# display.net
KiCad netlist of a schematic drawn in EAGLE
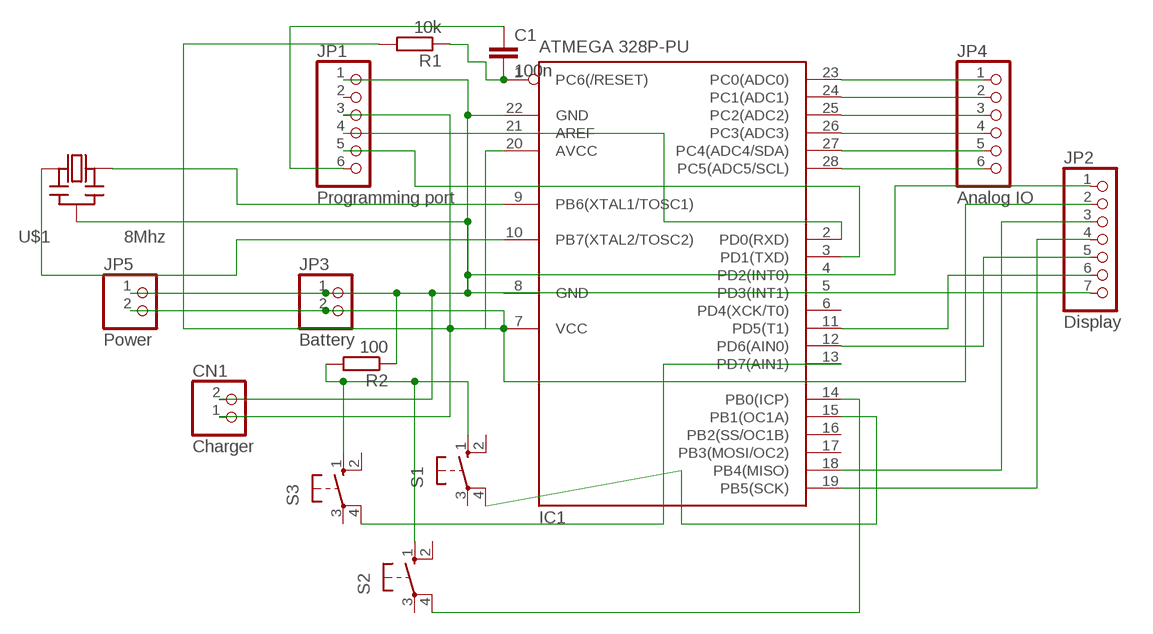
[diagram p0: schematic, sheet 1]

(export (version "E")
  (design (tool "Eeschema 10.0.6"))
  (components
    (comp (ref "C1")
      (value "100n")
      (footprint "eagle-import:C050-025X075")
      (libsource (lib "eagle-import") (part "C-EU050-025X075"))
    )
    (comp (ref "CN1")
      (value "Charger")
      (footprint "eagle-import:JST-PH-2-THM-RA")
      (libsource (lib "eagle-import") (part "JST_2PIN-THM-RA"))
    )
    (comp (ref "IC1")
      (value "ATMEGA 328P-PU")
      (footprint "eagle-import:DIL28-3")
      (libsource (lib "eagle-import") (part "MEGA8-P"))
    )
    (comp (ref "JP1")
      (value "Programming port")
      (footprint "eagle-import:1X06_90")
      (libsource (lib "eagle-import") (part "PINHD-1X6/90"))
    )
    (comp (ref "JP2")
      (value "Display")
      (footprint "eagle-import:1X07")
      (libsource (lib "eagle-import") (part "PINHD-1X7"))
    )
    (comp (ref "JP3")
      (value "Battery")
      (footprint "eagle-import:1X02")
      (libsource (lib "eagle-import") (part "PINHD-1X2"))
    )
    (comp (ref "JP4")
      (value "Analog IO")
      (footprint "eagle-import:1X06-CLEAN")
      (libsource (lib "eagle-import") (part "PINHD-1X6CLEAN"))
    )
    (comp (ref "JP5")
      (value "Power")
      (footprint "eagle-import:1X02")
      (libsource (lib "eagle-import") (part "PINHD-1X2"))
    )
    (comp (ref "R1")
      (value "10k")
      (footprint "eagle-import:0204_7")
      (libsource (lib "eagle-import") (part "R-EU_0204/7"))
    )
    (comp (ref "R2")
      (value "100")
      (footprint "eagle-import:0204_7")
      (libsource (lib "eagle-import") (part "R-EU_0204/7"))
    )
    (comp (ref "S1")
      (value "10-XX")
      (footprint "eagle-import:B3F-10XX")
      (fields (field (name "MPN") "B3F-1000"))
      (libsource (lib "eagle-import") (part "10-XX"))
    )
    (comp (ref "S2")
      (value "10-XX")
      (footprint "eagle-import:B3F-10XX")
      (fields
        (field (name "MPN") "B3F-1000")
        (field (name "MPN_1") "B3F-1000")
        (field (name "OC_FARNELL") "176432")
        (field (name "OC_NEWARK") "36M3542")
      )
      (libsource (lib "eagle-import") (part "10-XX"))
    )
    (comp (ref "S3")
      (value "10-XX")
      (footprint "eagle-import:B3F-10XX")
      (fields (field (name "MPN") "B3F-1000"))
      (libsource (lib "eagle-import") (part "10-XX"))
    )
    (comp (ref "U$1")
      (value "8Mhz")
      (footprint "eagle-import:CERM_OSC")
      (libsource (lib "eagle-import") (part "CERMOSCILL-THM"))
    )
  )
  (nets
    (net (code "1") (name "Net-(C1-Pad1)") (class "Default")
      (node (ref "C1") (pin "1") (pinfunction "1_1") (pintype "passive"))
      (node (ref "JP1") (pin "6") (pinfunction "6_6") (pintype "passive"))
    )
    (net (code "2") (name "Net-(CN1-1)") (class "Default")
      (node (ref "CN1") (pin "2") (pinfunction "1_2") (pintype "passive"))
      (node (ref "IC1") (pin "22") (pinfunction "GND_22") (pintype "power_in"))
      (node (ref "IC1") (pin "8") (pinfunction "GND_8") (pintype "power_in"))
      (node (ref "JP1") (pin "1") (pinfunction "1_1") (pintype "passive"))
      (node (ref "JP2") (pin "1") (pinfunction "1_1") (pintype "passive"))
      (node (ref "JP2") (pin "7") (pinfunction "7_7") (pintype "passive"))
      (node (ref "JP3") (pin "1") (pinfunction "1_1") (pintype "passive"))
      (node (ref "JP5") (pin "1") (pinfunction "1_1") (pintype "passive"))
      (node (ref "R2") (pin "1") (pinfunction "1_1") (pintype "passive"))
      (node (ref "U$1") (pin "P$2") (pinfunction "GND_P$2") (pintype "bidirectional"))
    )
    (net (code "3") (name "Net-(CN1-2)") (class "Default")
      (node (ref "CN1") (pin "1") (pinfunction "2_1") (pintype "passive"))
      (node (ref "IC1") (pin "20") (pinfunction "AVCC_20") (pintype "power_in"))
      (node (ref "IC1") (pin "7") (pinfunction "VCC_7") (pintype "power_in"))
      (node (ref "JP1") (pin "3") (pinfunction "3_3") (pintype "passive"))
      (node (ref "JP2") (pin "2") (pinfunction "2_2") (pintype "passive"))
      (node (ref "JP3") (pin "2") (pinfunction "2_2") (pintype "passive"))
      (node (ref "JP5") (pin "2") (pinfunction "2_2") (pintype "passive"))
      (node (ref "R1") (pin "2") (pinfunction "2_2") (pintype "passive"))
    )
    (net (code "4") (name "Net-(IC1-PB0(ICP))") (class "Default")
      (node (ref "IC1") (pin "14") (pinfunction "PB0(ICP)_14") (pintype "bidirectional"))
      (node (ref "S2") (pin "4") (pinfunction "P1_4") (pintype "passive"))
    )
    (net (code "5") (name "Net-(IC1-PB1(OC1A))") (class "Default")
      (node (ref "IC1") (pin "15") (pinfunction "PB1(OC1A)_15") (pintype "bidirectional"))
      (node (ref "S1") (pin "4") (pinfunction "P1_4") (pintype "passive"))
    )
    (net (code "6") (name "Net-(IC1-PB4(MISO))") (class "Default")
      (node (ref "IC1") (pin "18") (pinfunction "PB4(MISO)_18") (pintype "bidirectional"))
      (node (ref "JP2") (pin "3") (pinfunction "3_3") (pintype "passive"))
    )
    (net (code "7") (name "Net-(IC1-PB5(SCK))") (class "Default")
      (node (ref "IC1") (pin "19") (pinfunction "PB5(SCK)_19") (pintype "bidirectional"))
      (node (ref "JP2") (pin "4") (pinfunction "4_4") (pintype "passive"))
    )
    (net (code "8") (name "Net-(IC1-PB6(XTAL1{slash}TOSC1))") (class "Default")
      (node (ref "IC1") (pin "9") (pinfunction "PB6(XTAL1/TOSC1)_9") (pintype "bidirectional"))
      (node (ref "U$1") (pin "P$3") (pinfunction "OUT_P$3") (pintype "bidirectional"))
    )
    (net (code "9") (name "Net-(IC1-PB7(XTAL2{slash}TOSC2))") (class "Default")
      (node (ref "IC1") (pin "10") (pinfunction "PB7(XTAL2/TOSC2)_10") (pintype "bidirectional"))
      (node (ref "U$1") (pin "P$1") (pinfunction "IN_P$1") (pintype "bidirectional"))
    )
    (net (code "10") (name "Net-(IC1-PC0(ADC0))") (class "Default")
      (node (ref "IC1") (pin "23") (pinfunction "PC0(ADC0)_23") (pintype "bidirectional"))
      (node (ref "JP4") (pin "1") (pinfunction "1_1") (pintype "passive"))
    )
    (net (code "11") (name "Net-(IC1-PC1(ADC1))") (class "Default")
      (node (ref "IC1") (pin "24") (pinfunction "PC1(ADC1)_24") (pintype "bidirectional"))
      (node (ref "JP4") (pin "2") (pinfunction "2_2") (pintype "passive"))
    )
    (net (code "12") (name "Net-(IC1-PC2(ADC2))") (class "Default")
      (node (ref "IC1") (pin "25") (pinfunction "PC2(ADC2)_25") (pintype "bidirectional"))
      (node (ref "JP4") (pin "3") (pinfunction "3_3") (pintype "passive"))
    )
    (net (code "13") (name "Net-(IC1-PC3(ADC3))") (class "Default")
      (node (ref "IC1") (pin "26") (pinfunction "PC3(ADC3)_26") (pintype "bidirectional"))
      (node (ref "JP4") (pin "4") (pinfunction "4_4") (pintype "passive"))
    )
    (net (code "14") (name "Net-(IC1-PC4(ADC4{slash}SDA))") (class "Default")
      (node (ref "IC1") (pin "27") (pinfunction "PC4(ADC4/SDA)_27") (pintype "bidirectional"))
      (node (ref "JP4") (pin "5") (pinfunction "5_5") (pintype "passive"))
    )
    (net (code "15") (name "Net-(IC1-PC5(ADC5{slash}SCL))") (class "Default")
      (node (ref "IC1") (pin "28") (pinfunction "PC5(ADC5/SCL)_28") (pintype "bidirectional"))
      (node (ref "JP4") (pin "6") (pinfunction "6_6") (pintype "passive"))
    )
    (net (code "16") (name "Net-(IC1-PC6({slash}RESET))") (class "Default")
      (node (ref "C1") (pin "2") (pinfunction "2_2") (pintype "passive"))
      (node (ref "IC1") (pin "1") (pinfunction "PC6(/RESET)_1") (pintype "bidirectional"))
      (node (ref "R1") (pin "1") (pinfunction "1_1") (pintype "passive"))
    )
    (net (code "17") (name "Net-(IC1-PD0(RXD))") (class "Default")
      (node (ref "IC1") (pin "2") (pinfunction "PD0(RXD)_2") (pintype "bidirectional"))
      (node (ref "JP1") (pin "4") (pinfunction "4_4") (pintype "passive"))
    )
    (net (code "18") (name "Net-(IC1-PD1(TXD))") (class "Default")
      (node (ref "IC1") (pin "3") (pinfunction "PD1(TXD)_3") (pintype "bidirectional"))
      (node (ref "JP1") (pin "5") (pinfunction "5_5") (pintype "passive"))
    )
    (net (code "19") (name "Net-(IC1-PD5(T1))") (class "Default")
      (node (ref "IC1") (pin "11") (pinfunction "PD5(T1)_11") (pintype "bidirectional"))
      (node (ref "JP2") (pin "6") (pinfunction "6_6") (pintype "passive"))
    )
    (net (code "20") (name "Net-(IC1-PD6(AIN0))") (class "Default")
      (node (ref "IC1") (pin "12") (pinfunction "PD6(AIN0)_12") (pintype "bidirectional"))
      (node (ref "JP2") (pin "5") (pinfunction "5_5") (pintype "passive"))
    )
    (net (code "21") (name "Net-(IC1-PD7(AIN1))") (class "Default")
      (node (ref "IC1") (pin "13") (pinfunction "PD7(AIN1)_13") (pintype "bidirectional"))
      (node (ref "S3") (pin "4") (pinfunction "P1_4") (pintype "passive"))
    )
    (net (code "22") (name "Net-(S1-S)") (class "Default")
      (node (ref "R2") (pin "2") (pinfunction "2_2") (pintype "passive"))
      (node (ref "S1") (pin "1") (pinfunction "S_1") (pintype "passive"))
      (node (ref "S2") (pin "1") (pinfunction "S_1") (pintype "passive"))
      (node (ref "S3") (pin "1") (pinfunction "S_1") (pintype "passive"))
    )
    (net (code "23") (name "unconnected-(IC1-AREF-Pad21)") (class "Default")
      (node (ref "IC1") (pin "21") (pinfunction "AREF_21") (pintype "passive"))
    )
    (net (code "24") (name "unconnected-(IC1-PB2(SS{slash}OC1B)-Pad16)") (class "Default")
      (node (ref "IC1") (pin "16") (pinfunction "PB2(SS/OC1B)_16") (pintype "bidirectional"))
    )
    (net (code "25") (name "unconnected-(IC1-PB3(MOSI{slash}OC2)-Pad17)") (class "Default")
      (node (ref "IC1") (pin "17") (pinfunction "PB3(MOSI/OC2)_17") (pintype "bidirectional"))
    )
    (net (code "26") (name "unconnected-(IC1-PD2(INT0)-Pad4)") (class "Default")
      (node (ref "IC1") (pin "4") (pinfunction "PD2(INT0)_4") (pintype "bidirectional"))
    )
    (net (code "27") (name "unconnected-(IC1-PD3(INT1)-Pad5)") (class "Default")
      (node (ref "IC1") (pin "5") (pinfunction "PD3(INT1)_5") (pintype "bidirectional"))
    )
    (net (code "28") (name "unconnected-(IC1-PD4(XCK{slash}T0)-Pad6)") (class "Default")
      (node (ref "IC1") (pin "6") (pinfunction "PD4(XCK/T0)_6") (pintype "bidirectional"))
    )
    (net (code "29") (name "unconnected-(JP1-Pad2)") (class "Default")
      (node (ref "JP1") (pin "2") (pinfunction "2_2") (pintype "passive"))
    )
    (net (code "30") (name "unconnected-(S1-P-Pad3)") (class "Default")
      (node (ref "S1") (pin "3") (pinfunction "P_3") (pintype "passive"))
    )
    (net (code "31") (name "unconnected-(S1-S1-Pad2)") (class "Default")
      (node (ref "S1") (pin "2") (pinfunction "S1_2") (pintype "passive"))
    )
    (net (code "32") (name "unconnected-(S2-P-Pad3)") (class "Default")
      (node (ref "S2") (pin "3") (pinfunction "P_3") (pintype "passive"))
    )
    (net (code "33") (name "unconnected-(S2-S1-Pad2)") (class "Default")
      (node (ref "S2") (pin "2") (pinfunction "S1_2") (pintype "passive"))
    )
    (net (code "34") (name "unconnected-(S3-P-Pad3)") (class "Default")
      (node (ref "S3") (pin "3") (pinfunction "P_3") (pintype "passive"))
    )
    (net (code "35") (name "unconnected-(S3-S1-Pad2)") (class "Default")
      (node (ref "S3") (pin "2") (pinfunction "S1_2") (pintype "passive"))
    )
  )
)
